# watson.net
KiCad netlist of a schematic drawn in EAGLE
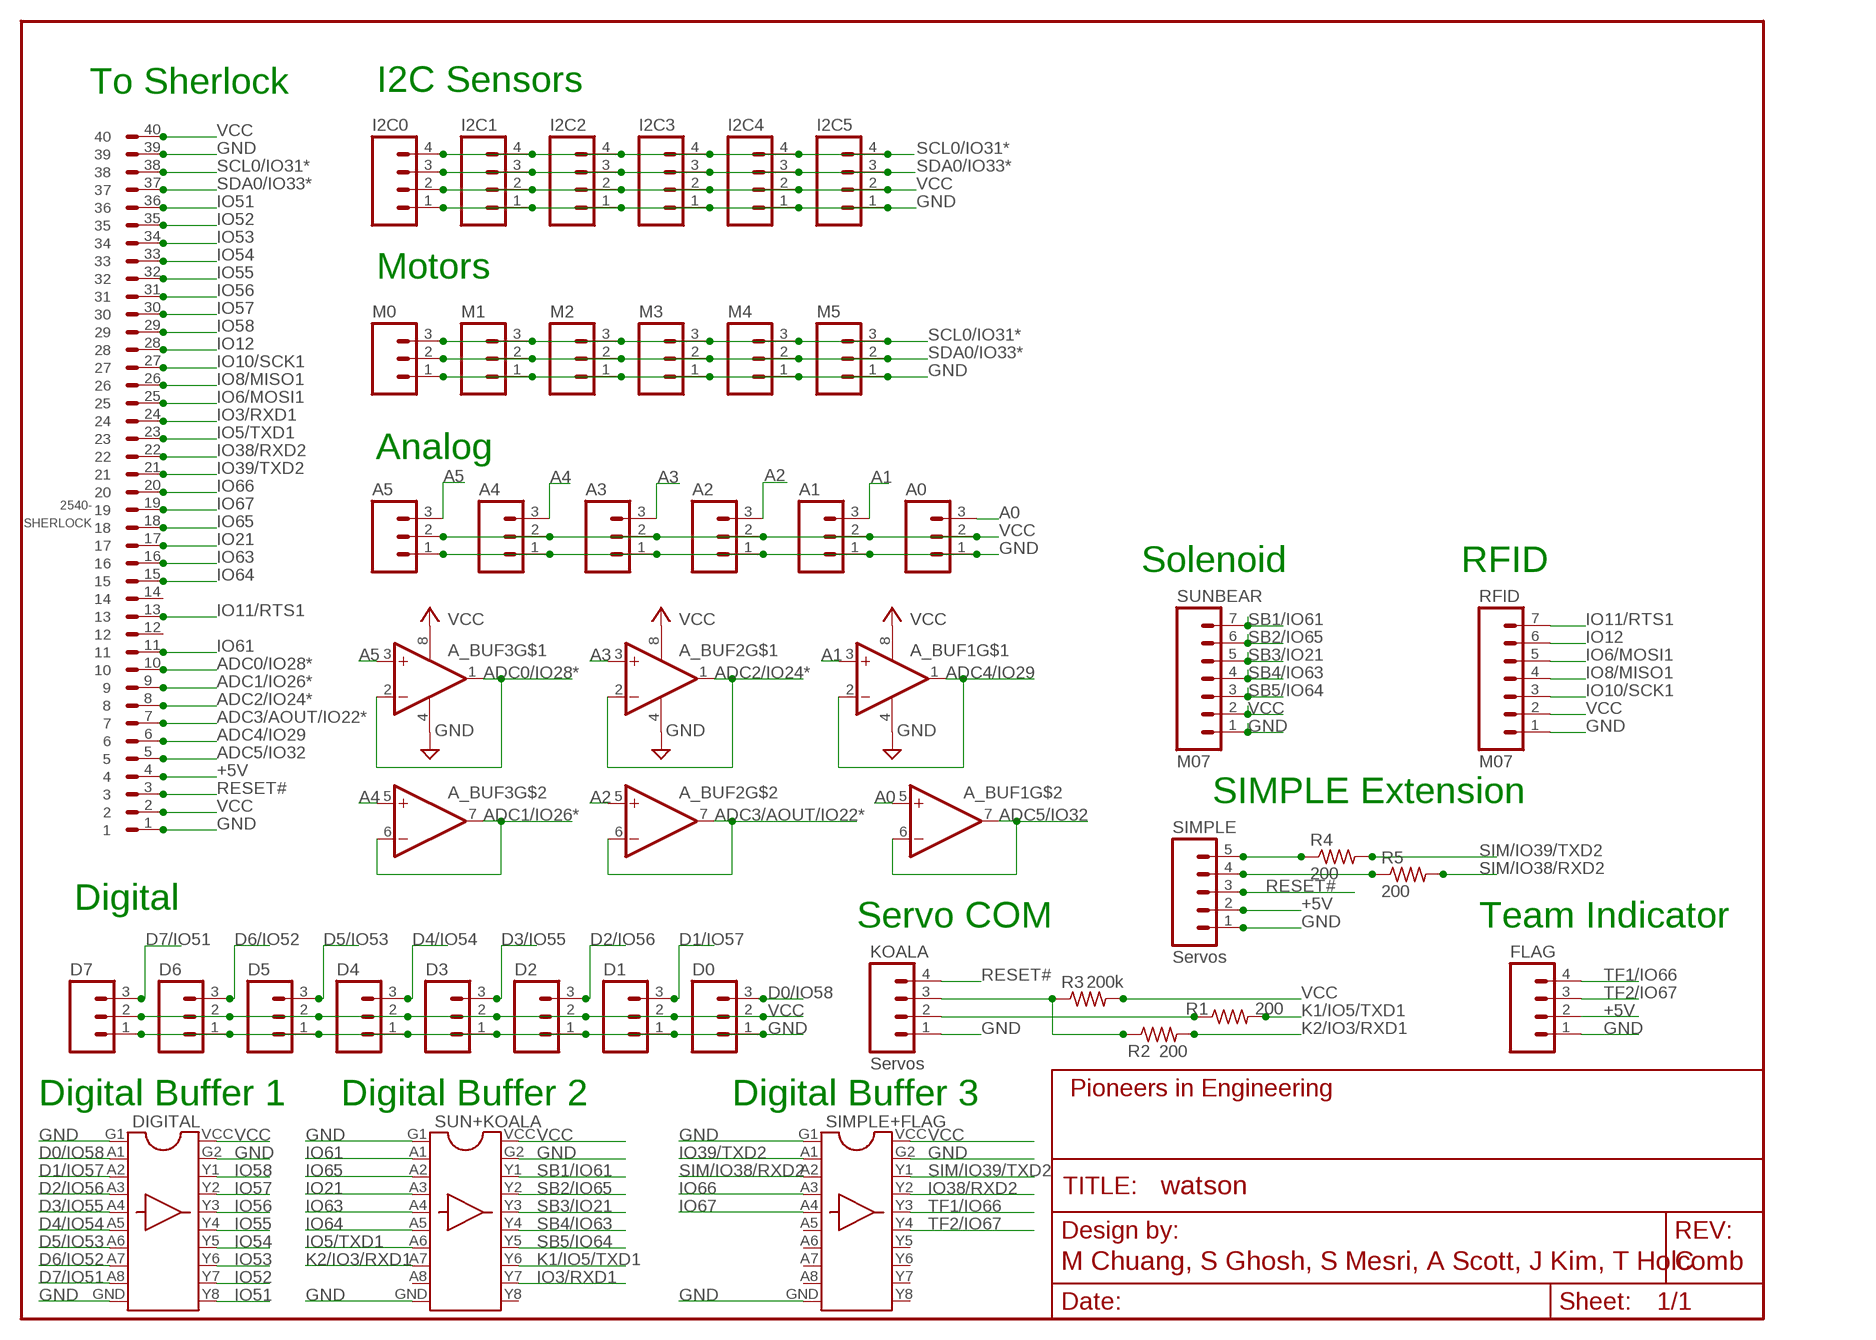
[diagram p0: schematic, sheet 1]

(export (version "E")
  (design (tool "Eeschema 10.0.6"))
  (components
    (comp (ref "A0")
      (value "M031X03-MTA")
      (footprint "eagle-import:1X03-MTA")
      (fields (field (name "PARTNUMBER") "A19470-ND"))
      (libsource (lib "eagle-import") (part "M031X03-MTA"))
    )
    (comp (ref "A1")
      (value "M031X03-MTA")
      (footprint "eagle-import:1X03-MTA")
      (fields (field (name "PARTNUMBER") "A19470-ND"))
      (libsource (lib "eagle-import") (part "M031X03-MTA"))
    )
    (comp (ref "A2")
      (value "M031X03-MTA")
      (footprint "eagle-import:1X03-MTA")
      (fields (field (name "PARTNUMBER") "A19470-ND"))
      (libsource (lib "eagle-import") (part "M031X03-MTA"))
    )
    (comp (ref "A3")
      (value "M031X03-MTA")
      (footprint "eagle-import:1X03-MTA")
      (fields (field (name "PARTNUMBER") "A19470-ND"))
      (libsource (lib "eagle-import") (part "M031X03-MTA"))
    )
    (comp (ref "A4")
      (value "M031X03-MTA")
      (footprint "eagle-import:1X03-MTA")
      (fields (field (name "PARTNUMBER") "A19470-ND"))
      (libsource (lib "eagle-import") (part "M031X03-MTA"))
    )
    (comp (ref "A5")
      (value "M031X03-MTA")
      (footprint "eagle-import:1X03-MTA")
      (fields (field (name "PARTNUMBER") "A19470-ND"))
      (libsource (lib "eagle-import") (part "M031X03-MTA"))
    )
    (comp (ref "A_BUF1")
      (value "OPAMP_DUALSOCKET")
      (footprint "eagle-import:OPAMP_DUAL_DIL")
      (libsource (lib "eagle-import") (part "OPAMP_DUALSOCKET"))
    )
    (comp (ref "A_BUF2")
      (value "OPAMP_DUALSOCKET")
      (footprint "eagle-import:OPAMP_DUAL_DIL")
      (libsource (lib "eagle-import") (part "OPAMP_DUALSOCKET"))
    )
    (comp (ref "A_BUF3")
      (value "OPAMP_DUALSOCKET")
      (footprint "eagle-import:OPAMP_DUAL_DIL")
      (libsource (lib "eagle-import") (part "OPAMP_DUALSOCKET"))
    )
    (comp (ref "D0")
      (value "M031X03-MTA")
      (footprint "eagle-import:1X03-MTA")
      (fields (field (name "PARTNUMBER") "A19470-ND"))
      (libsource (lib "eagle-import") (part "M031X03-MTA"))
    )
    (comp (ref "D1")
      (value "M031X03-MTA")
      (footprint "eagle-import:1X03-MTA")
      (fields (field (name "PARTNUMBER") "A19470-ND"))
      (libsource (lib "eagle-import") (part "M031X03-MTA"))
    )
    (comp (ref "D2")
      (value "M031X03-MTA")
      (footprint "eagle-import:1X03-MTA")
      (fields (field (name "PARTNUMBER") "A19470-ND"))
      (libsource (lib "eagle-import") (part "M031X03-MTA"))
    )
    (comp (ref "D3")
      (value "M031X03-MTA")
      (footprint "eagle-import:1X03-MTA")
      (fields (field (name "PARTNUMBER") "A19470-ND"))
      (libsource (lib "eagle-import") (part "M031X03-MTA"))
    )
    (comp (ref "D4")
      (value "M031X03-MTA")
      (footprint "eagle-import:1X03-MTA")
      (fields (field (name "PARTNUMBER") "A19470-ND"))
      (libsource (lib "eagle-import") (part "M031X03-MTA"))
    )
    (comp (ref "D5")
      (value "M031X03-MTA")
      (footprint "eagle-import:1X03-MTA")
      (fields (field (name "PARTNUMBER") "A19470-ND"))
      (libsource (lib "eagle-import") (part "M031X03-MTA"))
    )
    (comp (ref "D6")
      (value "M031X03-MTA")
      (footprint "eagle-import:1X03-MTA")
      (fields (field (name "PARTNUMBER") "A19470-ND"))
      (libsource (lib "eagle-import") (part "M031X03-MTA"))
    )
    (comp (ref "D7")
      (value "M031X03-MTA")
      (footprint "eagle-import:1X03-MTA")
      (fields (field (name "PARTNUMBER") "A19470-ND"))
      (libsource (lib "eagle-import") (part "M031X03-MTA"))
    )
    (comp (ref "DIGITAL")
      (value "DIGITAL_BUFFERSOCKET")
      (footprint "eagle-import:DIGITAL_BUFFER_SOCKET")
      (libsource (lib "eagle-import") (part "DIGITAL_BUFFERSOCKET"))
    )
    (comp (ref "FLAG")
      (value "M041X04-MTA")
      (footprint "eagle-import:1X04-MTA")
      (fields (field (name "PARTNUMBER") "A1922-ND"))
      (libsource (lib "eagle-import") (part "M041X04-MTA"))
    )
    (comp (ref "I2C0")
      (value "M041X04-MTA")
      (footprint "eagle-import:1X04-MTA")
      (fields (field (name "PARTNUMBER") "A1922-ND"))
      (libsource (lib "eagle-import") (part "M041X04-MTA"))
    )
    (comp (ref "I2C1")
      (value "M041X04-MTA")
      (footprint "eagle-import:1X04-MTA")
      (fields (field (name "PARTNUMBER") "A1922-ND"))
      (libsource (lib "eagle-import") (part "M041X04-MTA"))
    )
    (comp (ref "I2C2")
      (value "M041X04-MTA")
      (footprint "eagle-import:1X04-MTA")
      (fields (field (name "PARTNUMBER") "A1922-ND"))
      (libsource (lib "eagle-import") (part "M041X04-MTA"))
    )
    (comp (ref "I2C3")
      (value "M041X04-MTA")
      (footprint "eagle-import:1X04-MTA")
      (fields (field (name "PARTNUMBER") "A1922-ND"))
      (libsource (lib "eagle-import") (part "M041X04-MTA"))
    )
    (comp (ref "I2C4")
      (value "M041X04-MTA")
      (footprint "eagle-import:1X04-MTA")
      (fields (field (name "PARTNUMBER") "A1922-ND"))
      (libsource (lib "eagle-import") (part "M041X04-MTA"))
    )
    (comp (ref "I2C5")
      (value "M041X04-MTA")
      (footprint "eagle-import:1X04-MTA")
      (fields (field (name "PARTNUMBER") "A1922-ND"))
      (libsource (lib "eagle-import") (part "M041X04-MTA"))
    )
    (comp (ref "KOALA")
      (value "Servos")
      (footprint "eagle-import:1X04-MTA")
      (fields (field (name "PARTNUMBER") "A1922-ND"))
      (libsource (lib "eagle-import") (part "M041X04-MTA"))
    )
    (comp (ref "M0")
      (value "M031X03-MTA")
      (footprint "eagle-import:1X03-MTA")
      (fields (field (name "PARTNUMBER") "A19470-ND"))
      (libsource (lib "eagle-import") (part "M031X03-MTA"))
    )
    (comp (ref "M1")
      (value "M031X03-MTA")
      (footprint "eagle-import:1X03-MTA")
      (fields (field (name "PARTNUMBER") "A19470-ND"))
      (libsource (lib "eagle-import") (part "M031X03-MTA"))
    )
    (comp (ref "M2")
      (value "M031X03-MTA")
      (footprint "eagle-import:1X03-MTA")
      (fields (field (name "PARTNUMBER") "A19470-ND"))
      (libsource (lib "eagle-import") (part "M031X03-MTA"))
    )
    (comp (ref "M3")
      (value "M031X03-MTA")
      (footprint "eagle-import:1X03-MTA")
      (fields (field (name "PARTNUMBER") "A19470-ND"))
      (libsource (lib "eagle-import") (part "M031X03-MTA"))
    )
    (comp (ref "M4")
      (value "M031X03-MTA")
      (footprint "eagle-import:1X03-MTA")
      (fields (field (name "PARTNUMBER") "A19470-ND"))
      (libsource (lib "eagle-import") (part "M031X03-MTA"))
    )
    (comp (ref "M5")
      (value "M031X03-MTA")
      (footprint "eagle-import:1X03-MTA")
      (fields (field (name "PARTNUMBER") "A19470-ND"))
      (libsource (lib "eagle-import") (part "M031X03-MTA"))
    )
    (comp (ref "R1")
      (value "200")
      (footprint "eagle-import:R0603")
      (libsource (lib "eagle-import") (part "R-US_R0603"))
    )
    (comp (ref "R2")
      (value "200")
      (footprint "eagle-import:R0603")
      (libsource (lib "eagle-import") (part "R-US_R0603"))
    )
    (comp (ref "R3")
      (value "200k")
      (footprint "eagle-import:R0603")
      (libsource (lib "eagle-import") (part "R-US_R0603"))
    )
    (comp (ref "R4")
      (value "200")
      (footprint "eagle-import:R0603")
      (libsource (lib "eagle-import") (part "R-US_R0603"))
    )
    (comp (ref "R5")
      (value "200")
      (footprint "eagle-import:R0603")
      (libsource (lib "eagle-import") (part "R-US_R0603"))
    )
    (comp (ref "RFID")
      (value "M07")
      (footprint "eagle-import:1X07-MTA")
      (fields (field (name "PARTNUMBER") "A19472-ND"))
      (libsource (lib "eagle-import") (part "M07"))
    )
    (comp (ref "SHERLOCK")
      (value "2540-")
      (footprint "eagle-import:PAK100_2500-40")
      (fields (field (name "PARTNUMBER") "S9175-ND"))
      (libsource (lib "eagle-import") (part "2540-"))
    )
    (comp (ref "SIMPLE")
      (value "Servos")
      (footprint "eagle-import:1X05-MTA")
      (fields (field (name "PARTNUMBER") "A19471-ND"))
      (libsource (lib "eagle-import") (part "M05MTA"))
    )
    (comp (ref "SIMPLE+FLAG")
      (value "DIGITAL_BUFFERSOCKET")
      (footprint "eagle-import:DIGITAL_BUFFER_SOCKET")
      (libsource (lib "eagle-import") (part "DIGITAL_BUFFERSOCKET"))
    )
    (comp (ref "SUN+KOALA")
      (value "DIGITAL_BUFFERSOCKET")
      (footprint "eagle-import:DIGITAL_BUFFER_SOCKET")
      (libsource (lib "eagle-import") (part "DIGITAL_BUFFERSOCKET"))
    )
    (comp (ref "SUNBEAR")
      (value "M07")
      (footprint "eagle-import:1X07-MTA")
      (fields (field (name "PARTNUMBER") "A19472-ND"))
      (libsource (lib "eagle-import") (part "M07"))
    )
  )
  (nets
    (net (code "1") (name "/+5V") (class "Default")
      (node (ref "FLAG") (pin "2") (pinfunction "2_2") (pintype "passive"))
      (node (ref "SHERLOCK") (pin "4") (pinfunction "4_4") (pintype "bidirectional"))
      (node (ref "SIMPLE") (pin "2") (pinfunction "2_2") (pintype "passive"))
    )
    (net (code "2") (name "/A0") (class "Default")
      (node (ref "A0") (pin "3") (pinfunction "3_3") (pintype "passive"))
      (node (ref "A_BUF1") (pin "5") (pinfunction "+IN_5") (pintype "input"))
    )
    (net (code "3") (name "/A1") (class "Default")
      (node (ref "A1") (pin "3") (pinfunction "3_3") (pintype "passive"))
      (node (ref "A_BUF1") (pin "3") (pinfunction "+IN_3") (pintype "input"))
    )
    (net (code "4") (name "/A2") (class "Default")
      (node (ref "A2") (pin "3") (pinfunction "3_3") (pintype "passive"))
      (node (ref "A_BUF2") (pin "5") (pinfunction "+IN_5") (pintype "input"))
    )
    (net (code "5") (name "/A3") (class "Default")
      (node (ref "A3") (pin "3") (pinfunction "3_3") (pintype "passive"))
      (node (ref "A_BUF2") (pin "3") (pinfunction "+IN_3") (pintype "input"))
    )
    (net (code "6") (name "/A4") (class "Default")
      (node (ref "A4") (pin "3") (pinfunction "3_3") (pintype "passive"))
      (node (ref "A_BUF3") (pin "5") (pinfunction "+IN_5") (pintype "input"))
    )
    (net (code "7") (name "/A5") (class "Default")
      (node (ref "A5") (pin "3") (pinfunction "3_3") (pintype "passive"))
      (node (ref "A_BUF3") (pin "3") (pinfunction "+IN_3") (pintype "input"))
    )
    (net (code "8") (name "/ADC0{slash}IO28*") (class "Default")
      (node (ref "A_BUF3") (pin "1") (pinfunction "OUT_1") (pintype "output"))
      (node (ref "A_BUF3") (pin "2") (pinfunction "-IN_2") (pintype "input"))
      (node (ref "SHERLOCK") (pin "10") (pinfunction "10_10") (pintype "bidirectional"))
    )
    (net (code "9") (name "/ADC1{slash}IO26*") (class "Default")
      (node (ref "A_BUF3") (pin "6") (pinfunction "-IN_6") (pintype "input"))
      (node (ref "A_BUF3") (pin "7") (pinfunction "OUT_7") (pintype "output"))
      (node (ref "SHERLOCK") (pin "9") (pinfunction "9_9") (pintype "bidirectional"))
    )
    (net (code "10") (name "/ADC2{slash}IO24*") (class "Default")
      (node (ref "A_BUF2") (pin "1") (pinfunction "OUT_1") (pintype "output"))
      (node (ref "A_BUF2") (pin "2") (pinfunction "-IN_2") (pintype "input"))
      (node (ref "SHERLOCK") (pin "8") (pinfunction "8_8") (pintype "bidirectional"))
    )
    (net (code "11") (name "/ADC3{slash}AOUT{slash}IO22*") (class "Default")
      (node (ref "A_BUF2") (pin "6") (pinfunction "-IN_6") (pintype "input"))
      (node (ref "A_BUF2") (pin "7") (pinfunction "OUT_7") (pintype "output"))
      (node (ref "SHERLOCK") (pin "7") (pinfunction "7_7") (pintype "bidirectional"))
    )
    (net (code "12") (name "/ADC4{slash}IO29") (class "Default")
      (node (ref "A_BUF1") (pin "1") (pinfunction "OUT_1") (pintype "output"))
      (node (ref "A_BUF1") (pin "2") (pinfunction "-IN_2") (pintype "input"))
      (node (ref "SHERLOCK") (pin "6") (pinfunction "6_6") (pintype "bidirectional"))
    )
    (net (code "13") (name "/ADC5{slash}IO32") (class "Default")
      (node (ref "A_BUF1") (pin "6") (pinfunction "-IN_6") (pintype "input"))
      (node (ref "A_BUF1") (pin "7") (pinfunction "OUT_7") (pintype "output"))
      (node (ref "SHERLOCK") (pin "5") (pinfunction "5_5") (pintype "bidirectional"))
    )
    (net (code "14") (name "/D0{slash}IO58") (class "Default")
      (node (ref "D0") (pin "3") (pinfunction "3_3") (pintype "passive"))
      (node (ref "DIGITAL") (pin "A1") (pinfunction "A1_A1") (pintype "passive"))
    )
    (net (code "15") (name "/D1{slash}IO57") (class "Default")
      (node (ref "D1") (pin "3") (pinfunction "3_3") (pintype "passive"))
      (node (ref "DIGITAL") (pin "A2") (pinfunction "A2_A2") (pintype "passive"))
    )
    (net (code "16") (name "/D2{slash}IO56") (class "Default")
      (node (ref "D2") (pin "3") (pinfunction "3_3") (pintype "passive"))
      (node (ref "DIGITAL") (pin "A3") (pinfunction "A3_A3") (pintype "passive"))
    )
    (net (code "17") (name "/D3{slash}IO55") (class "Default")
      (node (ref "D3") (pin "3") (pinfunction "3_3") (pintype "passive"))
      (node (ref "DIGITAL") (pin "A4") (pinfunction "A4_A4") (pintype "passive"))
    )
    (net (code "18") (name "/D4{slash}IO54") (class "Default")
      (node (ref "D4") (pin "3") (pinfunction "3_3") (pintype "passive"))
      (node (ref "DIGITAL") (pin "A5") (pinfunction "A5_A5") (pintype "passive"))
    )
    (net (code "19") (name "/D5{slash}IO53") (class "Default")
      (node (ref "D5") (pin "3") (pinfunction "3_3") (pintype "passive"))
      (node (ref "DIGITAL") (pin "A6") (pinfunction "A6_A6") (pintype "passive"))
    )
    (net (code "20") (name "/D6{slash}IO52") (class "Default")
      (node (ref "D6") (pin "3") (pinfunction "3_3") (pintype "passive"))
      (node (ref "DIGITAL") (pin "A7") (pinfunction "A7_A7") (pintype "passive"))
    )
    (net (code "21") (name "/D7{slash}IO51") (class "Default")
      (node (ref "D7") (pin "3") (pinfunction "3_3") (pintype "passive"))
      (node (ref "DIGITAL") (pin "A8") (pinfunction "A8_A8") (pintype "passive"))
    )
    (net (code "22") (name "/IO3{slash}RXD1") (class "Default")
      (node (ref "SHERLOCK") (pin "24") (pinfunction "24_24") (pintype "bidirectional"))
      (node (ref "SUN+KOALA") (pin "Y7") (pinfunction "Y7_Y7") (pintype "passive"))
    )
    (net (code "23") (name "/IO5{slash}TXD1") (class "Default")
      (node (ref "SHERLOCK") (pin "23") (pinfunction "23_23") (pintype "bidirectional"))
      (node (ref "SUN+KOALA") (pin "A6") (pinfunction "A6_A6") (pintype "passive"))
    )
    (net (code "24") (name "/IO6{slash}MOSI1") (class "Default")
      (node (ref "RFID") (pin "5") (pinfunction "5_5") (pintype "passive"))
      (node (ref "SHERLOCK") (pin "25") (pinfunction "25_25") (pintype "bidirectional"))
    )
    (net (code "25") (name "/IO8{slash}MISO1") (class "Default")
      (node (ref "RFID") (pin "4") (pinfunction "4_4") (pintype "passive"))
      (node (ref "SHERLOCK") (pin "26") (pinfunction "26_26") (pintype "bidirectional"))
    )
    (net (code "26") (name "/IO10{slash}SCK1") (class "Default")
      (node (ref "RFID") (pin "3") (pinfunction "3_3") (pintype "passive"))
      (node (ref "SHERLOCK") (pin "27") (pinfunction "27_27") (pintype "bidirectional"))
    )
    (net (code "27") (name "/IO11{slash}RTS1") (class "Default")
      (node (ref "RFID") (pin "7") (pinfunction "7_7") (pintype "passive"))
      (node (ref "SHERLOCK") (pin "13") (pinfunction "13_13") (pintype "bidirectional"))
    )
    (net (code "28") (name "/IO12") (class "Default")
      (node (ref "RFID") (pin "6") (pinfunction "6_6") (pintype "passive"))
      (node (ref "SHERLOCK") (pin "28") (pinfunction "28_28") (pintype "bidirectional"))
    )
    (net (code "29") (name "/IO21") (class "Default")
      (node (ref "SHERLOCK") (pin "17") (pinfunction "17_17") (pintype "bidirectional"))
      (node (ref "SUN+KOALA") (pin "A3") (pinfunction "A3_A3") (pintype "passive"))
    )
    (net (code "30") (name "/IO38{slash}RXD2") (class "Default")
      (node (ref "SHERLOCK") (pin "22") (pinfunction "22_22") (pintype "bidirectional"))
      (node (ref "SIMPLE+FLAG") (pin "Y2") (pinfunction "Y2_Y2") (pintype "passive"))
    )
    (net (code "31") (name "/IO39{slash}TXD2") (class "Default")
      (node (ref "SHERLOCK") (pin "21") (pinfunction "21_21") (pintype "bidirectional"))
      (node (ref "SIMPLE+FLAG") (pin "A1") (pinfunction "A1_A1") (pintype "passive"))
    )
    (net (code "32") (name "/IO51") (class "Default")
      (node (ref "DIGITAL") (pin "Y8") (pinfunction "Y8_Y8") (pintype "passive"))
      (node (ref "SHERLOCK") (pin "36") (pinfunction "36_36") (pintype "bidirectional"))
    )
    (net (code "33") (name "/IO52") (class "Default")
      (node (ref "DIGITAL") (pin "Y7") (pinfunction "Y7_Y7") (pintype "passive"))
      (node (ref "SHERLOCK") (pin "35") (pinfunction "35_35") (pintype "bidirectional"))
    )
    (net (code "34") (name "/IO53") (class "Default")
      (node (ref "DIGITAL") (pin "Y6") (pinfunction "Y6_Y6") (pintype "passive"))
      (node (ref "SHERLOCK") (pin "34") (pinfunction "34_34") (pintype "bidirectional"))
    )
    (net (code "35") (name "/IO54") (class "Default")
      (node (ref "DIGITAL") (pin "Y5") (pinfunction "Y5_Y5") (pintype "passive"))
      (node (ref "SHERLOCK") (pin "33") (pinfunction "33_33") (pintype "bidirectional"))
    )
    (net (code "36") (name "/IO55") (class "Default")
      (node (ref "DIGITAL") (pin "Y4") (pinfunction "Y4_Y4") (pintype "passive"))
      (node (ref "SHERLOCK") (pin "32") (pinfunction "32_32") (pintype "bidirectional"))
    )
    (net (code "37") (name "/IO56") (class "Default")
      (node (ref "DIGITAL") (pin "Y3") (pinfunction "Y3_Y3") (pintype "passive"))
      (node (ref "SHERLOCK") (pin "31") (pinfunction "31_31") (pintype "bidirectional"))
    )
    (net (code "38") (name "/IO57") (class "Default")
      (node (ref "DIGITAL") (pin "Y2") (pinfunction "Y2_Y2") (pintype "passive"))
      (node (ref "SHERLOCK") (pin "30") (pinfunction "30_30") (pintype "bidirectional"))
    )
    (net (code "39") (name "/IO58") (class "Default")
      (node (ref "DIGITAL") (pin "Y1") (pinfunction "Y1_Y1") (pintype "passive"))
      (node (ref "SHERLOCK") (pin "29") (pinfunction "29_29") (pintype "bidirectional"))
    )
    (net (code "40") (name "/IO61") (class "Default")
      (node (ref "SHERLOCK") (pin "11") (pinfunction "11_11") (pintype "bidirectional"))
      (node (ref "SUN+KOALA") (pin "A1") (pinfunction "A1_A1") (pintype "passive"))
    )
    (net (code "41") (name "/IO63") (class "Default")
      (node (ref "SHERLOCK") (pin "16") (pinfunction "16_16") (pintype "bidirectional"))
      (node (ref "SUN+KOALA") (pin "A4") (pinfunction "A4_A4") (pintype "passive"))
    )
    (net (code "42") (name "/IO64") (class "Default")
      (node (ref "SHERLOCK") (pin "15") (pinfunction "15_15") (pintype "bidirectional"))
      (node (ref "SUN+KOALA") (pin "A5") (pinfunction "A5_A5") (pintype "passive"))
    )
    (net (code "43") (name "/IO65") (class "Default")
      (node (ref "SHERLOCK") (pin "18") (pinfunction "18_18") (pintype "bidirectional"))
      (node (ref "SUN+KOALA") (pin "A2") (pinfunction "A2_A2") (pintype "passive"))
    )
    (net (code "44") (name "/IO66") (class "Default")
      (node (ref "SHERLOCK") (pin "20") (pinfunction "20_20") (pintype "bidirectional"))
      (node (ref "SIMPLE+FLAG") (pin "A3") (pinfunction "A3_A3") (pintype "passive"))
    )
    (net (code "45") (name "/IO67") (class "Default")
      (node (ref "SHERLOCK") (pin "19") (pinfunction "19_19") (pintype "bidirectional"))
      (node (ref "SIMPLE+FLAG") (pin "A4") (pinfunction "A4_A4") (pintype "passive"))
    )
    (net (code "46") (name "/K1{slash}IO5{slash}TXD1") (class "Default")
      (node (ref "R1") (pin "2") (pinfunction "2_2") (pintype "passive"))
      (node (ref "SUN+KOALA") (pin "Y6") (pinfunction "Y6_Y6") (pintype "passive"))
    )
    (net (code "47") (name "/K2{slash}IO3{slash}RXD1") (class "Default")
      (node (ref "R2") (pin "2") (pinfunction "2_2") (pintype "passive"))
      (node (ref "SUN+KOALA") (pin "A7") (pinfunction "A7_A7") (pintype "passive"))
    )
    (net (code "48") (name "/RESET#") (class "Default")
      (node (ref "KOALA") (pin "4") (pinfunction "4_4") (pintype "passive"))
      (node (ref "SHERLOCK") (pin "3") (pinfunction "3_3") (pintype "bidirectional"))
      (node (ref "SIMPLE") (pin "3") (pinfunction "3_3") (pintype "passive"))
    )
    (net (code "49") (name "/SB1{slash}IO61") (class "Default")
      (node (ref "SUN+KOALA") (pin "Y1") (pinfunction "Y1_Y1") (pintype "passive"))
      (node (ref "SUNBEAR") (pin "7") (pinfunction "7_7") (pintype "passive"))
    )
    (net (code "50") (name "/SB2{slash}IO65") (class "Default")
      (node (ref "SUN+KOALA") (pin "Y2") (pinfunction "Y2_Y2") (pintype "passive"))
      (node (ref "SUNBEAR") (pin "6") (pinfunction "6_6") (pintype "passive"))
    )
    (net (code "51") (name "/SB3{slash}IO21") (class "Default")
      (node (ref "SUN+KOALA") (pin "Y3") (pinfunction "Y3_Y3") (pintype "passive"))
      (node (ref "SUNBEAR") (pin "5") (pinfunction "5_5") (pintype "passive"))
    )
    (net (code "52") (name "/SB4{slash}IO63") (class "Default")
      (node (ref "SUN+KOALA") (pin "Y4") (pinfunction "Y4_Y4") (pintype "passive"))
      (node (ref "SUNBEAR") (pin "4") (pinfunction "4_4") (pintype "passive"))
    )
    (net (code "53") (name "/SB5{slash}IO64") (class "Default")
      (node (ref "SUN+KOALA") (pin "Y5") (pinfunction "Y5_Y5") (pintype "passive"))
      (node (ref "SUNBEAR") (pin "3") (pinfunction "3_3") (pintype "passive"))
    )
    (net (code "54") (name "/SCL0{slash}IO31*") (class "Default")
      (node (ref "I2C0") (pin "4") (pinfunction "4_4") (pintype "passive"))
      (node (ref "I2C1") (pin "4") (pinfunction "4_4") (pintype "passive"))
      (node (ref "I2C2") (pin "4") (pinfunction "4_4") (pintype "passive"))
      (node (ref "I2C3") (pin "4") (pinfunction "4_4") (pintype "passive"))
      (node (ref "I2C4") (pin "4") (pinfunction "4_4") (pintype "passive"))
      (node (ref "I2C5") (pin "4") (pinfunction "4_4") (pintype "passive"))
      (node (ref "M0") (pin "3") (pinfunction "3_3") (pintype "passive"))
      (node (ref "M1") (pin "3") (pinfunction "3_3") (pintype "passive"))
      (node (ref "M2") (pin "3") (pinfunction "3_3") (pintype "passive"))
      (node (ref "M3") (pin "3") (pinfunction "3_3") (pintype "passive"))
      (node (ref "M4") (pin "3") (pinfunction "3_3") (pintype "passive"))
      (node (ref "M5") (pin "3") (pinfunction "3_3") (pintype "passive"))
      (node (ref "SHERLOCK") (pin "38") (pinfunction "38_38") (pintype "bidirectional"))
    )
    (net (code "55") (name "/SDA0{slash}IO33*") (class "Default")
      (node (ref "I2C0") (pin "3") (pinfunction "3_3") (pintype "passive"))
      (node (ref "I2C1") (pin "3") (pinfunction "3_3") (pintype "passive"))
      (node (ref "I2C2") (pin "3") (pinfunction "3_3") (pintype "passive"))
      (node (ref "I2C3") (pin "3") (pinfunction "3_3") (pintype "passive"))
      (node (ref "I2C4") (pin "3") (pinfunction "3_3") (pintype "passive"))
      (node (ref "I2C5") (pin "3") (pinfunction "3_3") (pintype "passive"))
      (node (ref "M0") (pin "2") (pinfunction "2_2") (pintype "passive"))
      (node (ref "M1") (pin "2") (pinfunction "2_2") (pintype "passive"))
      (node (ref "M2") (pin "2") (pinfunction "2_2") (pintype "passive"))
      (node (ref "M3") (pin "2") (pinfunction "2_2") (pintype "passive"))
      (node (ref "M4") (pin "2") (pinfunction "2_2") (pintype "passive"))
      (node (ref "M5") (pin "2") (pinfunction "2_2") (pintype "passive"))
      (node (ref "SHERLOCK") (pin "37") (pinfunction "37_37") (pintype "bidirectional"))
    )
    (net (code "56") (name "/SIM{slash}IO38{slash}RXD2") (class "Default")
      (node (ref "R5") (pin "2") (pinfunction "2_2") (pintype "passive"))
      (node (ref "SIMPLE+FLAG") (pin "A2") (pinfunction "A2_A2") (pintype "passive"))
    )
    (net (code "57") (name "/SIM{slash}IO39{slash}TXD2") (class "Default")
      (node (ref "R4") (pin "2") (pinfunction "2_2") (pintype "passive"))
      (node (ref "SIMPLE+FLAG") (pin "Y1") (pinfunction "Y1_Y1") (pintype "passive"))
    )
    (net (code "58") (name "/TF1{slash}IO66") (class "Default")
      (node (ref "FLAG") (pin "4") (pinfunction "4_4") (pintype "passive"))
      (node (ref "SIMPLE+FLAG") (pin "Y3") (pinfunction "Y3_Y3") (pintype "passive"))
    )
    (net (code "59") (name "/TF2{slash}IO67") (class "Default")
      (node (ref "FLAG") (pin "3") (pinfunction "3_3") (pintype "passive"))
      (node (ref "SIMPLE+FLAG") (pin "Y4") (pinfunction "Y4_Y4") (pintype "passive"))
    )
    (net (code "60") (name "GND") (class "Default")
      (node (ref "A0") (pin "1") (pinfunction "1_1") (pintype "passive"))
      (node (ref "A1") (pin "1") (pinfunction "1_1") (pintype "passive"))
      (node (ref "A2") (pin "1") (pinfunction "1_1") (pintype "passive"))
      (node (ref "A3") (pin "1") (pinfunction "1_1") (pintype "passive"))
      (node (ref "A4") (pin "1") (pinfunction "1_1") (pintype "passive"))
      (node (ref "A5") (pin "1") (pinfunction "1_1") (pintype "passive"))
      (node (ref "A_BUF1") (pin "4") (pinfunction "V-_4") (pintype "power_in"))
      (node (ref "A_BUF2") (pin "4") (pinfunction "V-_4") (pintype "power_in"))
      (node (ref "A_BUF3") (pin "4") (pinfunction "V-_4") (pintype "power_in"))
      (node (ref "D0") (pin "1") (pinfunction "1_1") (pintype "passive"))
      (node (ref "D1") (pin "1") (pinfunction "1_1") (pintype "passive"))
      (node (ref "D2") (pin "1") (pinfunction "1_1") (pintype "passive"))
      (node (ref "D3") (pin "1") (pinfunction "1_1") (pintype "passive"))
      (node (ref "D4") (pin "1") (pinfunction "1_1") (pintype "passive"))
      (node (ref "D5") (pin "1") (pinfunction "1_1") (pintype "passive"))
      (node (ref "D6") (pin "1") (pinfunction "1_1") (pintype "passive"))
      (node (ref "D7") (pin "1") (pinfunction "1_1") (pintype "passive"))
      (node (ref "DIGITAL") (pin "G1") (pinfunction "G1_G1") (pintype "passive"))
      (node (ref "DIGITAL") (pin "G2") (pinfunction "G2_G2") (pintype "passive"))
      (node (ref "DIGITAL") (pin "GND") (pinfunction "GND_GND") (pintype "passive"))
      (node (ref "FLAG") (pin "1") (pinfunction "1_1") (pintype "passive"))
      (node (ref "I2C0") (pin "1") (pinfunction "1_1") (pintype "passive"))
      (node (ref "I2C1") (pin "1") (pinfunction "1_1") (pintype "passive"))
      (node (ref "I2C2") (pin "1") (pinfunction "1_1") (pintype "passive"))
      (node (ref "I2C3") (pin "1") (pinfunction "1_1") (pintype "passive"))
      (node (ref "I2C4") (pin "1") (pinfunction "1_1") (pintype "passive"))
      (node (ref "I2C5") (pin "1") (pinfunction "1_1") (pintype "passive"))
      (node (ref "KOALA") (pin "1") (pinfunction "1_1") (pintype "passive"))
      (node (ref "M0") (pin "1") (pinfunction "1_1") (pintype "passive"))
      (node (ref "M1") (pin "1") (pinfunction "1_1") (pintype "passive"))
      (node (ref "M2") (pin "1") (pinfunction "1_1") (pintype "passive"))
      (node (ref "M3") (pin "1") (pinfunction "1_1") (pintype "passive"))
      (node (ref "M4") (pin "1") (pinfunction "1_1") (pintype "passive"))
      (node (ref "M5") (pin "1") (pinfunction "1_1") (pintype "passive"))
      (node (ref "RFID") (pin "1") (pinfunction "1_1") (pintype "passive"))
      (node (ref "SHERLOCK") (pin "1") (pinfunction "1_1") (pintype "bidirectional"))
      (node (ref "SHERLOCK") (pin "39") (pinfunction "39_39") (pintype "bidirectional"))
      (node (ref "SIMPLE") (pin "1") (pinfunction "1_1") (pintype "passive"))
      (node (ref "SIMPLE+FLAG") (pin "G1") (pinfunction "G1_G1") (pintype "passive"))
      (node (ref "SIMPLE+FLAG") (pin "G2") (pinfunction "G2_G2") (pintype "passive"))
      (node (ref "SIMPLE+FLAG") (pin "GND") (pinfunction "GND_GND") (pintype "passive"))
      (node (ref "SUN+KOALA") (pin "G1") (pinfunction "G1_G1") (pintype "passive"))
      (node (ref "SUN+KOALA") (pin "G2") (pinfunction "G2_G2") (pintype "passive"))
      (node (ref "SUN+KOALA") (pin "GND") (pinfunction "GND_GND") (pintype "passive"))
      (node (ref "SUNBEAR") (pin "1") (pinfunction "1_1") (pintype "passive"))
    )
    (net (code "61") (name "Net-(KOALA-Pad2)") (class "Default")
      (node (ref "KOALA") (pin "2") (pinfunction "2_2") (pintype "passive"))
      (node (ref "R1") (pin "1") (pinfunction "1_1") (pintype "passive"))
    )
    (net (code "62") (name "Net-(KOALA-Pad3)") (class "Default")
      (node (ref "KOALA") (pin "3") (pinfunction "3_3") (pintype "passive"))
      (node (ref "R2") (pin "1") (pinfunction "1_1") (pintype "passive"))
      (node (ref "R3") (pin "1") (pinfunction "1_1") (pintype "passive"))
    )
    (net (code "63") (name "Net-(R4-Pad1)") (class "Default")
      (node (ref "R4") (pin "1") (pinfunction "1_1") (pintype "passive"))
      (node (ref "SIMPLE") (pin "5") (pinfunction "5_5") (pintype "passive"))
    )
    (net (code "64") (name "Net-(R5-Pad1)") (class "Default")
      (node (ref "R5") (pin "1") (pinfunction "1_1") (pintype "passive"))
      (node (ref "SIMPLE") (pin "4") (pinfunction "4_4") (pintype "passive"))
    )
    (net (code "65") (name "VCC") (class "Default")
      (node (ref "A0") (pin "2") (pinfunction "2_2") (pintype "passive"))
      (node (ref "A1") (pin "2") (pinfunction "2_2") (pintype "passive"))
      (node (ref "A2") (pin "2") (pinfunction "2_2") (pintype "passive"))
      (node (ref "A3") (pin "2") (pinfunction "2_2") (pintype "passive"))
      (node (ref "A4") (pin "2") (pinfunction "2_2") (pintype "passive"))
      (node (ref "A5") (pin "2") (pinfunction "2_2") (pintype "passive"))
      (node (ref "A_BUF1") (pin "8") (pinfunction "V+_8") (pintype "power_in"))
      (node (ref "A_BUF2") (pin "8") (pinfunction "V+_8") (pintype "power_in"))
      (node (ref "A_BUF3") (pin "8") (pinfunction "V+_8") (pintype "power_in"))
      (node (ref "D0") (pin "2") (pinfunction "2_2") (pintype "passive"))
      (node (ref "D1") (pin "2") (pinfunction "2_2") (pintype "passive"))
      (node (ref "D2") (pin "2") (pinfunction "2_2") (pintype "passive"))
      (node (ref "D3") (pin "2") (pinfunction "2_2") (pintype "passive"))
      (node (ref "D4") (pin "2") (pinfunction "2_2") (pintype "passive"))
      (node (ref "D5") (pin "2") (pinfunction "2_2") (pintype "passive"))
      (node (ref "D6") (pin "2") (pinfunction "2_2") (pintype "passive"))
      (node (ref "D7") (pin "2") (pinfunction "2_2") (pintype "passive"))
      (node (ref "DIGITAL") (pin "VCC") (pinfunction "VCC_VCC") (pintype "passive"))
      (node (ref "I2C0") (pin "2") (pinfunction "2_2") (pintype "passive"))
      (node (ref "I2C1") (pin "2") (pinfunction "2_2") (pintype "passive"))
      (node (ref "I2C2") (pin "2") (pinfunction "2_2") (pintype "passive"))
      (node (ref "I2C3") (pin "2") (pinfunction "2_2") (pintype "passive"))
      (node (ref "I2C4") (pin "2") (pinfunction "2_2") (pintype "passive"))
      (node (ref "I2C5") (pin "2") (pinfunction "2_2") (pintype "passive"))
      (node (ref "R3") (pin "2") (pinfunction "2_2") (pintype "passive"))
      (node (ref "RFID") (pin "2") (pinfunction "2_2") (pintype "passive"))
      (node (ref "SHERLOCK") (pin "2") (pinfunction "2_2") (pintype "bidirectional"))
      (node (ref "SHERLOCK") (pin "40") (pinfunction "40_40") (pintype "bidirectional"))
      (node (ref "SIMPLE+FLAG") (pin "VCC") (pinfunction "VCC_VCC") (pintype "passive"))
      (node (ref "SUN+KOALA") (pin "VCC") (pinfunction "VCC_VCC") (pintype "passive"))
      (node (ref "SUNBEAR") (pin "2") (pinfunction "2_2") (pintype "passive"))
    )
    (net (code "66") (name "unconnected-(SHERLOCK-Pad12)") (class "Default")
      (node (ref "SHERLOCK") (pin "12") (pinfunction "12_12") (pintype "bidirectional"))
    )
    (net (code "67") (name "unconnected-(SHERLOCK-Pad14)") (class "Default")
      (node (ref "SHERLOCK") (pin "14") (pinfunction "14_14") (pintype "bidirectional"))
    )
    (net (code "68") (name "unconnected-(SIMPLE+FLAG-PadA5)") (class "Default")
      (node (ref "SIMPLE+FLAG") (pin "A5") (pinfunction "A5_A5") (pintype "passive"))
    )
    (net (code "69") (name "unconnected-(SIMPLE+FLAG-PadA6)") (class "Default")
      (node (ref "SIMPLE+FLAG") (pin "A6") (pinfunction "A6_A6") (pintype "passive"))
    )
    (net (code "70") (name "unconnected-(SIMPLE+FLAG-PadA7)") (class "Default")
      (node (ref "SIMPLE+FLAG") (pin "A7") (pinfunction "A7_A7") (pintype "passive"))
    )
    (net (code "71") (name "unconnected-(SIMPLE+FLAG-PadA8)") (class "Default")
      (node (ref "SIMPLE+FLAG") (pin "A8") (pinfunction "A8_A8") (pintype "passive"))
    )
    (net (code "72") (name "unconnected-(SIMPLE+FLAG-PadY5)") (class "Default")
      (node (ref "SIMPLE+FLAG") (pin "Y5") (pinfunction "Y5_Y5") (pintype "passive"))
    )
    (net (code "73") (name "unconnected-(SIMPLE+FLAG-PadY6)") (class "Default")
      (node (ref "SIMPLE+FLAG") (pin "Y6") (pinfunction "Y6_Y6") (pintype "passive"))
    )
    (net (code "74") (name "unconnected-(SIMPLE+FLAG-PadY7)") (class "Default")
      (node (ref "SIMPLE+FLAG") (pin "Y7") (pinfunction "Y7_Y7") (pintype "passive"))
    )
    (net (code "75") (name "unconnected-(SIMPLE+FLAG-PadY8)") (class "Default")
      (node (ref "SIMPLE+FLAG") (pin "Y8") (pinfunction "Y8_Y8") (pintype "passive"))
    )
    (net (code "76") (name "unconnected-(SUN+KOALA-PadA8)") (class "Default")
      (node (ref "SUN+KOALA") (pin "A8") (pinfunction "A8_A8") (pintype "passive"))
    )
    (net (code "77") (name "unconnected-(SUN+KOALA-PadY8)") (class "Default")
      (node (ref "SUN+KOALA") (pin "Y8") (pinfunction "Y8_Y8") (pintype "passive"))
    )
  )
)
